# primary_teensy.net
KiCad netlist of a schematic drawn in EAGLE
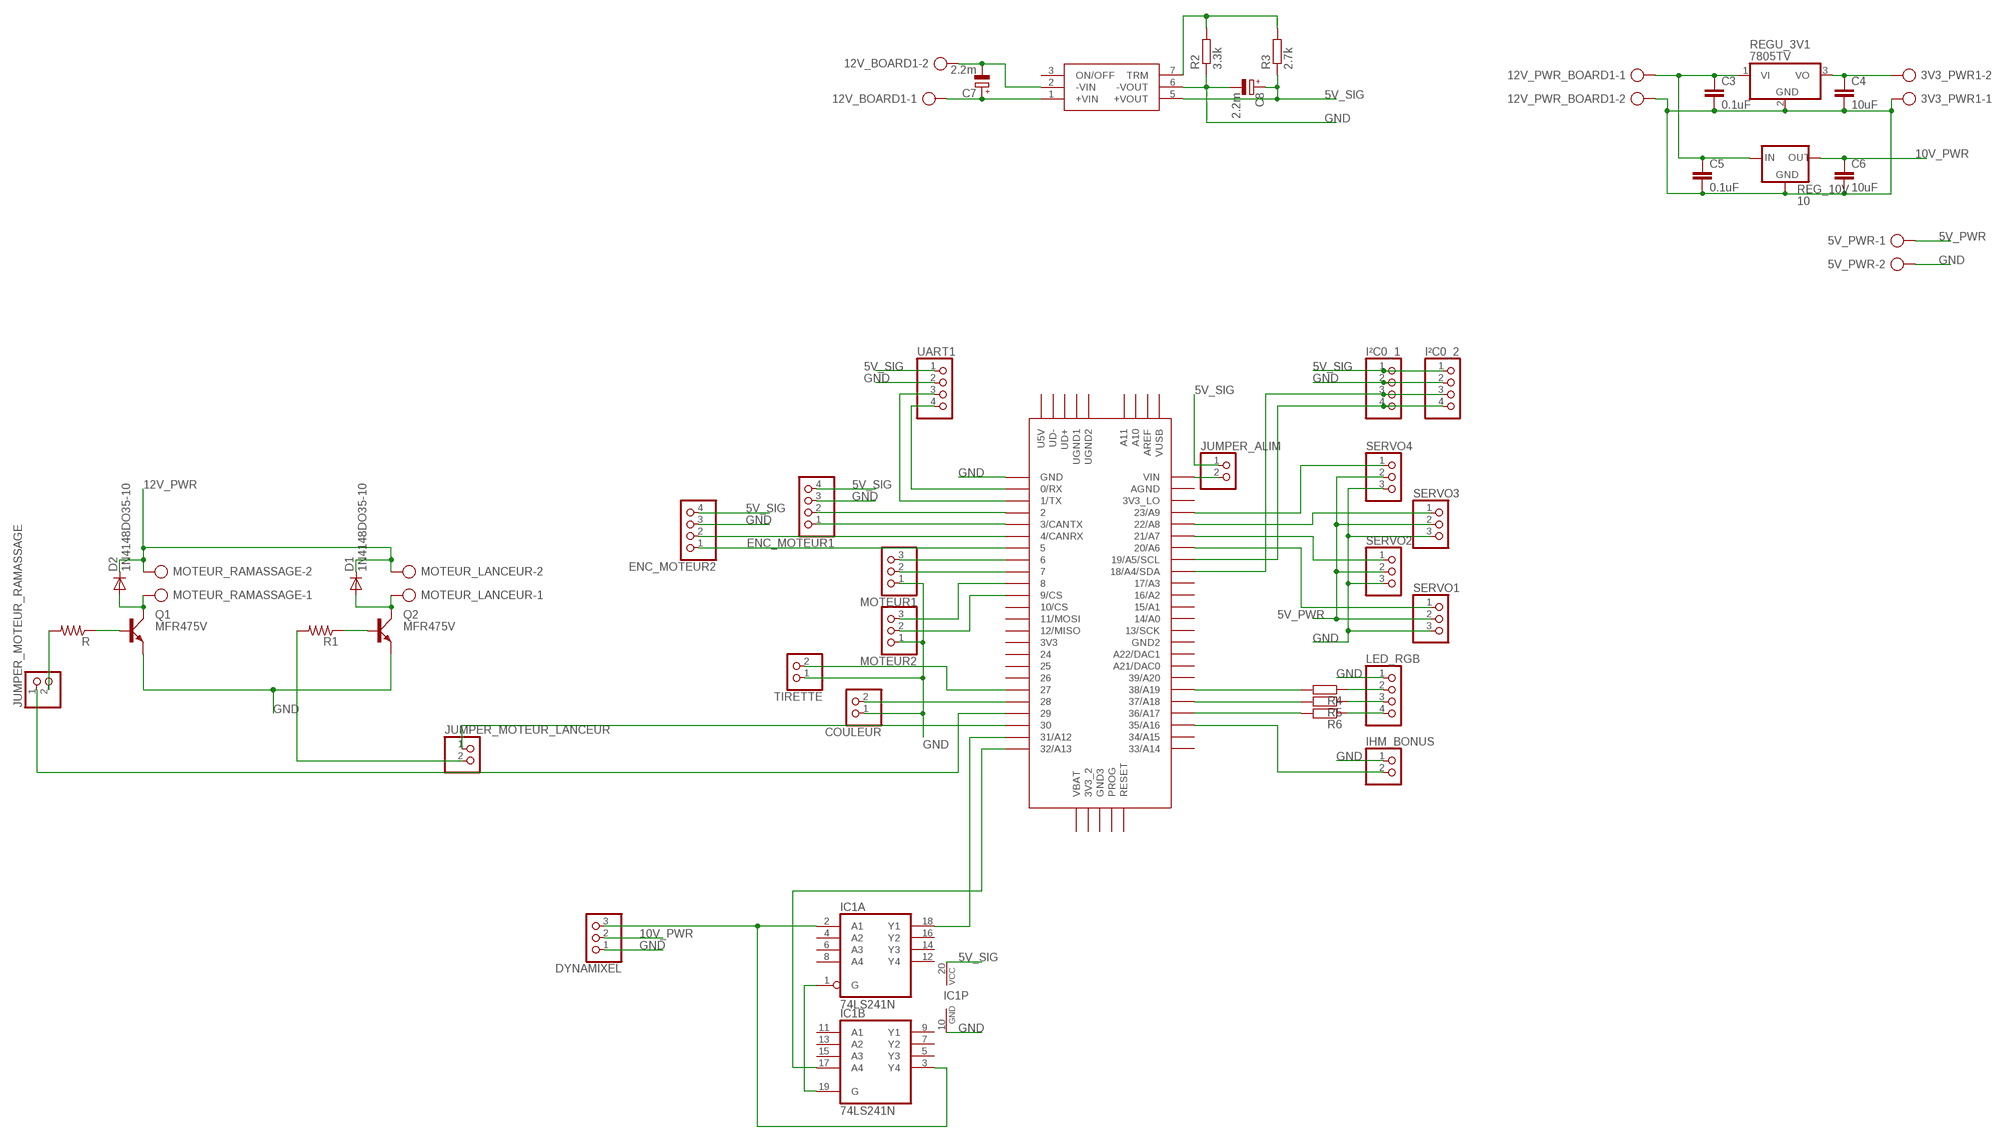
[diagram p0: schematic, sheet 1]

(export (version "E")
  (design (tool "Eeschema 10.0.6"))
  (components
    (comp (ref "3V3_PWR1")
      (value "AK300/2")
      (footprint "eagle-import:AK300_2")
      (fields (field (name "OC_FARNELL") "unknown") (field (name "OC_NEWARK") "unknown"))
      (libsource (lib "eagle-import") (part "AK300/2"))
    )
    (comp (ref "5V_PWR")
      (value "AK300/2")
      (footprint "eagle-import:AK300_2")
      (fields (field (name "OC_FARNELL") "unknown") (field (name "OC_NEWARK") "unknown"))
      (libsource (lib "eagle-import") (part "AK300/2"))
    )
    (comp (ref "12V_BOARD1")
      (value "AK300/2")
      (footprint "eagle-import:AK300_2")
      (fields (field (name "OC_FARNELL") "unknown") (field (name "OC_NEWARK") "unknown"))
      (libsource (lib "eagle-import") (part "AK300/2"))
    )
    (comp (ref "12V_PWR_BOARD1")
      (value "AK300/2")
      (footprint "eagle-import:AK300_2")
      (fields (field (name "OC_FARNELL") "unknown") (field (name "OC_NEWARK") "unknown"))
      (libsource (lib "eagle-import") (part "AK300/2"))
    )
    (comp (ref "C3")
      (value "0.1uF")
      (footprint "eagle-import:C050-025X075")
      (libsource (lib "eagle-import") (part "C-EU050-025X075"))
    )
    (comp (ref "C4")
      (value "10uF")
      (footprint "eagle-import:C050-025X075")
      (libsource (lib "eagle-import") (part "C-EU050-025X075"))
    )
    (comp (ref "C5")
      (value "0.1uF")
      (footprint "eagle-import:C050-025X075")
      (libsource (lib "eagle-import") (part "C-EU050-025X075"))
    )
    (comp (ref "C6")
      (value "10uF")
      (footprint "eagle-import:C050-025X075")
      (libsource (lib "eagle-import") (part "C-EU050-025X075"))
    )
    (comp (ref "C7")
      (value "2.2m")
      (footprint "eagle-import:E5-13")
      (libsource (lib "eagle-import") (part "CPOL-EUE5-13"))
    )
    (comp (ref "C8")
      (value "2.2m")
      (footprint "eagle-import:E5-13")
      (libsource (lib "eagle-import") (part "CPOL-EUE5-13"))
    )
    (comp (ref "COULEUR")
      (value "PINHD-1X2")
      (footprint "eagle-import:1X02")
      (libsource (lib "eagle-import") (part "PINHD-1X2"))
    )
    (comp (ref "D1")
      (value "1N4148DO35-10")
      (footprint "eagle-import:DO35-10")
      (libsource (lib "eagle-import") (part "1N4148DO35-10"))
    )
    (comp (ref "D2")
      (value "1N4148DO35-10")
      (footprint "eagle-import:DO35-10")
      (libsource (lib "eagle-import") (part "1N4148DO35-10"))
    )
    (comp (ref "DYNAMIXEL")
      (value "PINHD-1X3")
      (footprint "eagle-import:1X03")
      (libsource (lib "eagle-import") (part "PINHD-1X3"))
    )
    (comp (ref "ENC_MOTEUR1")
      (value "PINHD-1X4")
      (footprint "eagle-import:1X04")
      (libsource (lib "eagle-import") (part "PINHD-1X4"))
    )
    (comp (ref "ENC_MOTEUR2")
      (value "PINHD-1X4")
      (footprint "eagle-import:1X04")
      (libsource (lib "eagle-import") (part "PINHD-1X4"))
    )
    (comp (ref "IC1")
      (value "74LS241N")
      (footprint "eagle-import:DIL20")
      (libsource (lib "eagle-import") (part "74241NLS"))
    )
    (comp (ref "IHM_BONUS")
      (value "PINHD-1X2")
      (footprint "eagle-import:1X02")
      (libsource (lib "eagle-import") (part "PINHD-1X2"))
    )
    (comp (ref "I²C0_1")
      (value "PINHD-1X4")
      (footprint "eagle-import:1X04")
      (libsource (lib "eagle-import") (part "PINHD-1X4"))
    )
    (comp (ref "I²C0_2")
      (value "PINHD-1X4")
      (footprint "eagle-import:1X04")
      (libsource (lib "eagle-import") (part "PINHD-1X4"))
    )
    (comp (ref "JUMPER_ALIM")
      (value "PINHD-1X2")
      (footprint "eagle-import:1X02")
      (libsource (lib "eagle-import") (part "PINHD-1X2"))
    )
    (comp (ref "JUMPER_MOTEUR_LANCEUR")
      (value "PINHD-1X2")
      (footprint "eagle-import:1X02")
      (libsource (lib "eagle-import") (part "PINHD-1X2"))
    )
    (comp (ref "JUMPER_MOTEUR_RAMASSAGE")
      (value "PINHD-1X2")
      (footprint "eagle-import:1X02")
      (libsource (lib "eagle-import") (part "PINHD-1X2"))
    )
    (comp (ref "LED_RGB")
      (value "PINHD-1X4")
      (footprint "eagle-import:1X04")
      (libsource (lib "eagle-import") (part "PINHD-1X4"))
    )
    (comp (ref "MOTEUR1")
      (value "PINHD-1X3")
      (footprint "eagle-import:1X03")
      (libsource (lib "eagle-import") (part "PINHD-1X3"))
    )
    (comp (ref "MOTEUR2")
      (value "PINHD-1X3")
      (footprint "eagle-import:1X03")
      (libsource (lib "eagle-import") (part "PINHD-1X3"))
    )
    (comp (ref "MOTEUR_LANCEUR")
      (value "AK300/2")
      (footprint "eagle-import:AK300_2")
      (fields (field (name "OC_FARNELL") "unknown") (field (name "OC_NEWARK") "unknown"))
      (libsource (lib "eagle-import") (part "AK300/2"))
    )
    (comp (ref "MOTEUR_RAMASSAGE")
      (value "AK300/2")
      (footprint "eagle-import:AK300_2")
      (fields (field (name "OC_FARNELL") "unknown") (field (name "OC_NEWARK") "unknown"))
      (libsource (lib "eagle-import") (part "AK300/2"))
    )
    (comp (ref "Q1")
      (value "MFR475V")
      (footprint "eagle-import:TO220AV")
      (libsource (lib "eagle-import") (part "MFR4V75"))
    )
    (comp (ref "Q2")
      (value "MFR475V")
      (footprint "eagle-import:TO220AV")
      (libsource (lib "eagle-import") (part "MFR4V75"))
    )
    (comp (ref "R")
      (value "RESISTORAXIAL-0.3")
      (footprint "eagle-import:AXIAL-0.3")
      (libsource (lib "eagle-import") (part "RESISTORAXIAL-0.3"))
    )
    (comp (ref "R1")
      (value "RESISTORAXIAL-0.3")
      (footprint "eagle-import:AXIAL-0.3")
      (libsource (lib "eagle-import") (part "RESISTORAXIAL-0.3"))
    )
    (comp (ref "R2")
      (value "3.3k")
      (footprint "eagle-import:0207_7")
      (libsource (lib "eagle-import") (part "R-EU_0207/7"))
    )
    (comp (ref "R3")
      (value "2.7k")
      (footprint "eagle-import:0207_7")
      (libsource (lib "eagle-import") (part "R-EU_0207/7"))
    )
    (comp (ref "R4")
      (value "R-EU_0207/7")
      (footprint "eagle-import:0207_7")
      (libsource (lib "eagle-import") (part "R-EU_0207/7"))
    )
    (comp (ref "R5")
      (value "R-EU_0207/7")
      (footprint "eagle-import:0207_7")
      (libsource (lib "eagle-import") (part "R-EU_0207/7"))
    )
    (comp (ref "R6")
      (value "R-EU_0207/7")
      (footprint "eagle-import:0207_7")
      (libsource (lib "eagle-import") (part "R-EU_0207/7"))
    )
    (comp (ref "REGU_3V1")
      (value "7805TV")
      (footprint "eagle-import:TO220V")
      (libsource (lib "eagle-import") (part "78TV05"))
    )
    (comp (ref "REG_10V")
      (value "10")
      (footprint "eagle-import:78XXS")
      (libsource (lib "eagle-import") (part "78XXS"))
    )
    (comp (ref "SERVO1")
      (value "PINHD-1X3")
      (footprint "eagle-import:1X03")
      (libsource (lib "eagle-import") (part "PINHD-1X3"))
    )
    (comp (ref "SERVO2")
      (value "PINHD-1X3")
      (footprint "eagle-import:1X03")
      (libsource (lib "eagle-import") (part "PINHD-1X3"))
    )
    (comp (ref "SERVO3")
      (value "PINHD-1X3")
      (footprint "eagle-import:1X03")
      (libsource (lib "eagle-import") (part "PINHD-1X3"))
    )
    (comp (ref "SERVO4")
      (value "PINHD-1X3")
      (footprint "eagle-import:1X03")
      (libsource (lib "eagle-import") (part "PINHD-1X3"))
    )
    (comp (ref "TIRETTE")
      (value "PINHD-1X2")
      (footprint "eagle-import:1X02")
      (libsource (lib "eagle-import") (part "PINHD-1X2"))
    )
    (comp (ref "U$1")
      (value "TEENSY_3.5/3.6")
      (footprint "eagle-import:TEENSY_3.5_3.6")
      (libsource (lib "eagle-import") (part "TEENSY_3.5/3.6"))
    )
    (comp (ref "U$3")
      (value "TEN25-1211TEN25-1211")
      (footprint "eagle-import:TEN25")
      (libsource (lib "eagle-import") (part "TEN25-1211TEN25-1211"))
    )
    (comp (ref "UART1")
      (value "PINHD-1X4")
      (footprint "eagle-import:1X04")
      (libsource (lib "eagle-import") (part "PINHD-1X4"))
    )
  )
  (nets
    (net (code "1") (name "/5V_PWR") (class "Default")
      (node (ref "5V_PWR") (pin "1") (pinfunction "KL_1") (pintype "passive"))
      (node (ref "SERVO1") (pin "2") (pinfunction "2_2") (pintype "passive"))
      (node (ref "SERVO2") (pin "2") (pinfunction "2_2") (pintype "passive"))
      (node (ref "SERVO3") (pin "2") (pinfunction "2_2") (pintype "passive"))
      (node (ref "SERVO4") (pin "2") (pinfunction "2_2") (pintype "passive"))
    )
    (net (code "2") (name "/5V_SIG") (class "Default")
      (node (ref "C8") (pin "+") (pinfunction "+_+") (pintype "passive"))
      (node (ref "ENC_MOTEUR1") (pin "4") (pinfunction "4_4") (pintype "passive"))
      (node (ref "ENC_MOTEUR2") (pin "4") (pinfunction "4_4") (pintype "passive"))
      (node (ref "IC1") (pin "20") (pinfunction "VCC_20") (pintype "power_in"))
      (node (ref "I²C0_1") (pin "1") (pinfunction "1_1") (pintype "passive"))
      (node (ref "I²C0_2") (pin "1") (pinfunction "1_1") (pintype "passive"))
      (node (ref "JUMPER_ALIM") (pin "1") (pinfunction "1_1") (pintype "passive"))
      (node (ref "R3") (pin "1") (pinfunction "1_1") (pintype "passive"))
      (node (ref "U$3") (pin "5") (pinfunction "+VOUT_5") (pintype "bidirectional"))
      (node (ref "UART1") (pin "1") (pinfunction "1_1") (pintype "passive"))
    )
    (net (code "3") (name "/10V_PWR") (class "Default")
      (node (ref "C6") (pin "1") (pinfunction "1_1") (pintype "passive"))
      (node (ref "DYNAMIXEL") (pin "2") (pinfunction "2_2") (pintype "passive"))
      (node (ref "REG_10V") (pin "OUT") (pinfunction "OUT_OUT") (pintype "passive"))
    )
    (net (code "4") (name "/12V_PWR") (class "Default")
      (node (ref "12V_PWR_BOARD1") (pin "1") (pinfunction "KL_1") (pintype "passive"))
      (node (ref "C3") (pin "1") (pinfunction "1_1") (pintype "passive"))
      (node (ref "C5") (pin "1") (pinfunction "1_1") (pintype "passive"))
      (node (ref "D1") (pin "C") (pinfunction "C_C") (pintype "passive"))
      (node (ref "D2") (pin "C") (pinfunction "C_C") (pintype "passive"))
      (node (ref "MOTEUR_LANCEUR") (pin "2") (pinfunction "KL_2") (pintype "passive"))
      (node (ref "MOTEUR_RAMASSAGE") (pin "2") (pinfunction "KL_2") (pintype "passive"))
      (node (ref "REGU_3V1") (pin "1") (pinfunction "VI_1") (pintype "input"))
      (node (ref "REG_10V") (pin "IN") (pinfunction "IN_IN") (pintype "input"))
    )
    (net (code "5") (name "/GND") (class "Default")
      (node (ref "12V_PWR_BOARD1") (pin "2") (pinfunction "KL_2") (pintype "passive"))
      (node (ref "3V3_PWR1") (pin "1") (pinfunction "KL_1") (pintype "passive"))
      (node (ref "5V_PWR") (pin "2") (pinfunction "KL_2") (pintype "passive"))
      (node (ref "C3") (pin "2") (pinfunction "2_2") (pintype "passive"))
      (node (ref "C4") (pin "2") (pinfunction "2_2") (pintype "passive"))
      (node (ref "C5") (pin "2") (pinfunction "2_2") (pintype "passive"))
      (node (ref "C6") (pin "2") (pinfunction "2_2") (pintype "passive"))
      (node (ref "C8") (pin "-") (pinfunction "-_-") (pintype "passive"))
      (node (ref "COULEUR") (pin "1") (pinfunction "1_1") (pintype "passive"))
      (node (ref "DYNAMIXEL") (pin "1") (pinfunction "1_1") (pintype "passive"))
      (node (ref "ENC_MOTEUR1") (pin "3") (pinfunction "3_3") (pintype "passive"))
      (node (ref "ENC_MOTEUR2") (pin "3") (pinfunction "3_3") (pintype "passive"))
      (node (ref "IC1") (pin "10") (pinfunction "GND_10") (pintype "power_in"))
      (node (ref "IHM_BONUS") (pin "1") (pinfunction "1_1") (pintype "passive"))
      (node (ref "I²C0_1") (pin "2") (pinfunction "2_2") (pintype "passive"))
      (node (ref "I²C0_2") (pin "2") (pinfunction "2_2") (pintype "passive"))
      (node (ref "LED_RGB") (pin "1") (pinfunction "1_1") (pintype "passive"))
      (node (ref "MOTEUR1") (pin "1") (pinfunction "1_1") (pintype "passive"))
      (node (ref "MOTEUR2") (pin "1") (pinfunction "1_1") (pintype "passive"))
      (node (ref "Q1") (pin "E") (pinfunction "E_E") (pintype "passive"))
      (node (ref "Q2") (pin "E") (pinfunction "E_E") (pintype "passive"))
      (node (ref "R2") (pin "1") (pinfunction "1_1") (pintype "passive"))
      (node (ref "REGU_3V1") (pin "2") (pinfunction "GND_2") (pintype "passive"))
      (node (ref "REG_10V") (pin "GND") (pinfunction "GND_GND") (pintype "input"))
      (node (ref "SERVO1") (pin "3") (pinfunction "3_3") (pintype "passive"))
      (node (ref "SERVO2") (pin "3") (pinfunction "3_3") (pintype "passive"))
      (node (ref "SERVO3") (pin "3") (pinfunction "3_3") (pintype "passive"))
      (node (ref "SERVO4") (pin "3") (pinfunction "3_3") (pintype "passive"))
      (node (ref "TIRETTE") (pin "1") (pinfunction "1_1") (pintype "passive"))
      (node (ref "U$1") (pin "GND") (pinfunction "GND_GND") (pintype "bidirectional"))
      (node (ref "U$3") (pin "6") (pinfunction "-VOUT_6") (pintype "bidirectional"))
      (node (ref "UART1") (pin "2") (pinfunction "2_2") (pintype "passive"))
    )
    (net (code "6") (name "Net-(3V3_PWR1B-KL)") (class "Default")
      (node (ref "3V3_PWR1") (pin "2") (pinfunction "KL_2") (pintype "passive"))
      (node (ref "C4") (pin "1") (pinfunction "1_1") (pintype "passive"))
      (node (ref "REGU_3V1") (pin "3") (pinfunction "VO_3") (pintype "passive"))
    )
    (net (code "7") (name "Net-(12V_BOARD1A-KL)") (class "Default")
      (node (ref "12V_BOARD1") (pin "1") (pinfunction "KL_1") (pintype "passive"))
      (node (ref "C7") (pin "+") (pinfunction "+_+") (pintype "passive"))
      (node (ref "U$3") (pin "1") (pinfunction "+VIN_1") (pintype "bidirectional"))
    )
    (net (code "8") (name "Net-(12V_BOARD1B-KL)") (class "Default")
      (node (ref "12V_BOARD1") (pin "2") (pinfunction "KL_2") (pintype "passive"))
      (node (ref "C7") (pin "-") (pinfunction "-_-") (pintype "passive"))
      (node (ref "U$3") (pin "2") (pinfunction "-VIN_2") (pintype "bidirectional"))
    )
    (net (code "9") (name "Net-(COULEUR-Pad2)") (class "Default")
      (node (ref "COULEUR") (pin "2") (pinfunction "2_2") (pintype "passive"))
      (node (ref "U$1") (pin "28") (pinfunction "28_28") (pintype "bidirectional"))
    )
    (net (code "10") (name "Net-(ENC_MOTEUR1-Pad1)") (class "Default")
      (node (ref "ENC_MOTEUR1") (pin "1") (pinfunction "1_1") (pintype "passive"))
      (node (ref "U$1") (pin "3/CANTX") (pinfunction "3/CANTX_3/CANTX") (pintype "bidirectional"))
    )
    (net (code "11") (name "Net-(ENC_MOTEUR1-Pad2)") (class "Default")
      (node (ref "ENC_MOTEUR1") (pin "2") (pinfunction "2_2") (pintype "passive"))
      (node (ref "U$1") (pin "2") (pinfunction "2_2") (pintype "bidirectional"))
    )
    (net (code "12") (name "Net-(ENC_MOTEUR2-Pad1)") (class "Default")
      (node (ref "ENC_MOTEUR2") (pin "1") (pinfunction "1_1") (pintype "passive"))
      (node (ref "U$1") (pin "5") (pinfunction "5_5") (pintype "bidirectional"))
    )
    (net (code "13") (name "Net-(ENC_MOTEUR2-Pad2)") (class "Default")
      (node (ref "ENC_MOTEUR2") (pin "2") (pinfunction "2_2") (pintype "passive"))
      (node (ref "U$1") (pin "4/CANRX") (pinfunction "4/CANRX_4/CANRX") (pintype "bidirectional"))
    )
    (net (code "14") (name "Net-(IC1A-A1)") (class "Default")
      (node (ref "DYNAMIXEL") (pin "3") (pinfunction "3_3") (pintype "passive"))
      (node (ref "IC1") (pin "2") (pinfunction "A1_2") (pintype "input"))
      (node (ref "IC1") (pin "3") (pinfunction "Y4_3") (pintype "tri_state"))
    )
    (net (code "15") (name "Net-(IC1A-G)") (class "Default")
      (node (ref "IC1") (pin "1") (pinfunction "G_1") (pintype "input"))
      (node (ref "IC1") (pin "19") (pinfunction "G_19") (pintype "input"))
    )
    (net (code "16") (name "Net-(IC1A-Y1)") (class "Default")
      (node (ref "IC1") (pin "18") (pinfunction "Y1_18") (pintype "tri_state"))
      (node (ref "U$1") (pin "31/A12") (pinfunction "31/A12_31/A12") (pintype "bidirectional"))
    )
    (net (code "17") (name "Net-(IC1B-A4)") (class "Default")
      (node (ref "IC1") (pin "17") (pinfunction "A4_17") (pintype "input"))
      (node (ref "U$1") (pin "32/A13") (pinfunction "32/A13_32/A13") (pintype "bidirectional"))
    )
    (net (code "18") (name "Net-(IHM_BONUS-Pad2)") (class "Default")
      (node (ref "IHM_BONUS") (pin "2") (pinfunction "2_2") (pintype "passive"))
      (node (ref "U$1") (pin "35/A16") (pinfunction "35/A16_35/A16") (pintype "bidirectional"))
    )
    (net (code "19") (name "Net-(I²C0_1-Pad3)") (class "Default")
      (node (ref "I²C0_1") (pin "3") (pinfunction "3_3") (pintype "passive"))
      (node (ref "I²C0_2") (pin "3") (pinfunction "3_3") (pintype "passive"))
      (node (ref "U$1") (pin "18/A4/SDA") (pinfunction "18/A4/SDA_18/A4/SDA") (pintype "bidirectional"))
    )
    (net (code "20") (name "Net-(I²C0_1-Pad4)") (class "Default")
      (node (ref "I²C0_1") (pin "4") (pinfunction "4_4") (pintype "passive"))
      (node (ref "I²C0_2") (pin "4") (pinfunction "4_4") (pintype "passive"))
      (node (ref "U$1") (pin "19/A5/SCL") (pinfunction "19/A5/SCL_19/A5/SCL") (pintype "bidirectional"))
    )
    (net (code "21") (name "Net-(JUMPER_ALIM-Pad2)") (class "Default")
      (node (ref "JUMPER_ALIM") (pin "2") (pinfunction "2_2") (pintype "passive"))
      (node (ref "U$1") (pin "VIN") (pinfunction "VIN_VIN") (pintype "bidirectional"))
    )
    (net (code "22") (name "Net-(JUMPER_MOTEUR_LANCEUR-Pad1)") (class "Default")
      (node (ref "JUMPER_MOTEUR_LANCEUR") (pin "1") (pinfunction "1_1") (pintype "passive"))
      (node (ref "U$1") (pin "30") (pinfunction "30_30") (pintype "bidirectional"))
    )
    (net (code "23") (name "Net-(JUMPER_MOTEUR_RAMASSAGE-Pad1)") (class "Default")
      (node (ref "JUMPER_MOTEUR_RAMASSAGE") (pin "1") (pinfunction "1_1") (pintype "passive"))
      (node (ref "U$1") (pin "29") (pinfunction "29_29") (pintype "bidirectional"))
    )
    (net (code "24") (name "Net-(LED_RGB-Pad2)") (class "Default")
      (node (ref "LED_RGB") (pin "2") (pinfunction "2_2") (pintype "passive"))
      (node (ref "R4") (pin "1") (pinfunction "1_1") (pintype "passive"))
    )
    (net (code "25") (name "Net-(LED_RGB-Pad3)") (class "Default")
      (node (ref "LED_RGB") (pin "3") (pinfunction "3_3") (pintype "passive"))
      (node (ref "R5") (pin "1") (pinfunction "1_1") (pintype "passive"))
    )
    (net (code "26") (name "Net-(LED_RGB-Pad4)") (class "Default")
      (node (ref "LED_RGB") (pin "4") (pinfunction "4_4") (pintype "passive"))
      (node (ref "R6") (pin "1") (pinfunction "1_1") (pintype "passive"))
    )
    (net (code "27") (name "Net-(MOTEUR1-Pad2)") (class "Default")
      (node (ref "MOTEUR1") (pin "2") (pinfunction "2_2") (pintype "passive"))
      (node (ref "U$1") (pin "7") (pinfunction "7_7") (pintype "bidirectional"))
    )
    (net (code "28") (name "Net-(MOTEUR1-Pad3)") (class "Default")
      (node (ref "MOTEUR1") (pin "3") (pinfunction "3_3") (pintype "passive"))
      (node (ref "U$1") (pin "6") (pinfunction "6_6") (pintype "bidirectional"))
    )
    (net (code "29") (name "Net-(MOTEUR2-Pad2)") (class "Default")
      (node (ref "MOTEUR2") (pin "2") (pinfunction "2_2") (pintype "passive"))
      (node (ref "U$1") (pin "9/CS") (pinfunction "9/CS_9/CS") (pintype "bidirectional"))
    )
    (net (code "30") (name "Net-(MOTEUR2-Pad3)") (class "Default")
      (node (ref "MOTEUR2") (pin "3") (pinfunction "3_3") (pintype "passive"))
      (node (ref "U$1") (pin "8") (pinfunction "8_8") (pintype "bidirectional"))
    )
    (net (code "31") (name "Net-(MOTEUR_LANCEURA-KL)") (class "Default")
      (node (ref "D1") (pin "A") (pinfunction "A_A") (pintype "passive"))
      (node (ref "MOTEUR_LANCEUR") (pin "1") (pinfunction "KL_1") (pintype "passive"))
      (node (ref "Q2") (pin "C") (pinfunction "C_C") (pintype "passive"))
    )
    (net (code "32") (name "Net-(MOTEUR_RAMASSAGEA-KL)") (class "Default")
      (node (ref "D2") (pin "A") (pinfunction "A_A") (pintype "passive"))
      (node (ref "MOTEUR_RAMASSAGE") (pin "1") (pinfunction "KL_1") (pintype "passive"))
      (node (ref "Q1") (pin "C") (pinfunction "C_C") (pintype "passive"))
    )
    (net (code "33") (name "Net-(R-1)") (class "Default")
      (node (ref "Q1") (pin "B") (pinfunction "B_B") (pintype "passive"))
      (node (ref "R") (pin "P$1") (pinfunction "1_P$1") (pintype "passive"))
    )
    (net (code "34") (name "Net-(R-2)") (class "Default")
      (node (ref "JUMPER_MOTEUR_RAMASSAGE") (pin "2") (pinfunction "2_2") (pintype "passive"))
      (node (ref "R") (pin "P$2") (pinfunction "2_P$2") (pintype "passive"))
    )
    (net (code "35") (name "Net-(R1-1)") (class "Default")
      (node (ref "Q2") (pin "B") (pinfunction "B_B") (pintype "passive"))
      (node (ref "R1") (pin "P$1") (pinfunction "1_P$1") (pintype "passive"))
    )
    (net (code "36") (name "Net-(R1-2)") (class "Default")
      (node (ref "JUMPER_MOTEUR_LANCEUR") (pin "2") (pinfunction "2_2") (pintype "passive"))
      (node (ref "R1") (pin "P$2") (pinfunction "2_P$2") (pintype "passive"))
    )
    (net (code "37") (name "Net-(R4-Pad2)") (class "Default")
      (node (ref "R4") (pin "2") (pinfunction "2_2") (pintype "passive"))
      (node (ref "U$1") (pin "38/A19") (pinfunction "38/A19_38/A19") (pintype "bidirectional"))
    )
    (net (code "38") (name "Net-(R5-Pad2)") (class "Default")
      (node (ref "R5") (pin "2") (pinfunction "2_2") (pintype "passive"))
      (node (ref "U$1") (pin "37/A18") (pinfunction "37/A18_37/A18") (pintype "bidirectional"))
    )
    (net (code "39") (name "Net-(R6-Pad2)") (class "Default")
      (node (ref "R6") (pin "2") (pinfunction "2_2") (pintype "passive"))
      (node (ref "U$1") (pin "36/A17") (pinfunction "36/A17_36/A17") (pintype "bidirectional"))
    )
    (net (code "40") (name "Net-(SERVO1-Pad1)") (class "Default")
      (node (ref "SERVO1") (pin "1") (pinfunction "1_1") (pintype "passive"))
      (node (ref "U$1") (pin "20/A6") (pinfunction "20/A6_20/A6") (pintype "bidirectional"))
    )
    (net (code "41") (name "Net-(SERVO2-Pad1)") (class "Default")
      (node (ref "SERVO2") (pin "1") (pinfunction "1_1") (pintype "passive"))
      (node (ref "U$1") (pin "21/A7") (pinfunction "21/A7_21/A7") (pintype "bidirectional"))
    )
    (net (code "42") (name "Net-(SERVO3-Pad1)") (class "Default")
      (node (ref "SERVO3") (pin "1") (pinfunction "1_1") (pintype "passive"))
      (node (ref "U$1") (pin "22/A8") (pinfunction "22/A8_22/A8") (pintype "bidirectional"))
    )
    (net (code "43") (name "Net-(SERVO4-Pad1)") (class "Default")
      (node (ref "SERVO4") (pin "1") (pinfunction "1_1") (pintype "passive"))
      (node (ref "U$1") (pin "23/A9") (pinfunction "23/A9_23/A9") (pintype "bidirectional"))
    )
    (net (code "44") (name "Net-(TIRETTE-Pad2)") (class "Default")
      (node (ref "TIRETTE") (pin "2") (pinfunction "2_2") (pintype "passive"))
      (node (ref "U$1") (pin "27") (pinfunction "27_27") (pintype "bidirectional"))
    )
    (net (code "45") (name "Net-(U$1-Pad0{slash}RX)") (class "Default")
      (node (ref "U$1") (pin "0/RX") (pinfunction "0/RX_0/RX") (pintype "bidirectional"))
      (node (ref "UART1") (pin "4") (pinfunction "4_4") (pintype "passive"))
    )
    (net (code "46") (name "Net-(U$1-Pad1{slash}TX)") (class "Default")
      (node (ref "U$1") (pin "1/TX") (pinfunction "1/TX_1/TX") (pintype "bidirectional"))
      (node (ref "UART1") (pin "3") (pinfunction "3_3") (pintype "passive"))
    )
    (net (code "47") (name "Net-(U$3-TRM)") (class "Default")
      (node (ref "R2") (pin "2") (pinfunction "2_2") (pintype "passive"))
      (node (ref "R3") (pin "2") (pinfunction "2_2") (pintype "passive"))
      (node (ref "U$3") (pin "7") (pinfunction "TRM_7") (pintype "bidirectional"))
    )
    (net (code "48") (name "unconnected-(IC1A-A2-Pad4)") (class "Default")
      (node (ref "IC1") (pin "4") (pinfunction "A2_4") (pintype "input"))
    )
    (net (code "49") (name "unconnected-(IC1A-A3-Pad6)") (class "Default")
      (node (ref "IC1") (pin "6") (pinfunction "A3_6") (pintype "input"))
    )
    (net (code "50") (name "unconnected-(IC1A-A4-Pad8)") (class "Default")
      (node (ref "IC1") (pin "8") (pinfunction "A4_8") (pintype "input"))
    )
    (net (code "51") (name "unconnected-(IC1A-Y2-Pad16)") (class "Default")
      (node (ref "IC1") (pin "16") (pinfunction "Y2_16") (pintype "tri_state"))
    )
    (net (code "52") (name "unconnected-(IC1A-Y3-Pad14)") (class "Default")
      (node (ref "IC1") (pin "14") (pinfunction "Y3_14") (pintype "tri_state"))
    )
    (net (code "53") (name "unconnected-(IC1A-Y4-Pad12)") (class "Default")
      (node (ref "IC1") (pin "12") (pinfunction "Y4_12") (pintype "tri_state"))
    )
    (net (code "54") (name "unconnected-(IC1B-A1-Pad11)") (class "Default")
      (node (ref "IC1") (pin "11") (pinfunction "A1_11") (pintype "input"))
    )
    (net (code "55") (name "unconnected-(IC1B-A2-Pad13)") (class "Default")
      (node (ref "IC1") (pin "13") (pinfunction "A2_13") (pintype "input"))
    )
    (net (code "56") (name "unconnected-(IC1B-A3-Pad15)") (class "Default")
      (node (ref "IC1") (pin "15") (pinfunction "A3_15") (pintype "input"))
    )
    (net (code "57") (name "unconnected-(IC1B-Y1-Pad9)") (class "Default")
      (node (ref "IC1") (pin "9") (pinfunction "Y1_9") (pintype "tri_state"))
    )
    (net (code "58") (name "unconnected-(IC1B-Y2-Pad7)") (class "Default")
      (node (ref "IC1") (pin "7") (pinfunction "Y2_7") (pintype "tri_state"))
    )
    (net (code "59") (name "unconnected-(IC1B-Y3-Pad5)") (class "Default")
      (node (ref "IC1") (pin "5") (pinfunction "Y3_5") (pintype "tri_state"))
    )
    (net (code "60") (name "unconnected-(U$1-A21{slash}DAC0-Pad21{slash}DAC0)") (class "Default")
      (node (ref "U$1") (pin "21/DAC0") (pinfunction "A21/DAC0_21/DAC0") (pintype "bidirectional"))
    )
    (net (code "61") (name "unconnected-(U$1-Pad3V3)") (class "Default")
      (node (ref "U$1") (pin "3V3") (pinfunction "3V3_3V3") (pintype "bidirectional"))
    )
    (net (code "62") (name "unconnected-(U$1-Pad3V3_2)") (class "Default")
      (node (ref "U$1") (pin "3V3_2") (pinfunction "3V3_2_3V3_2") (pintype "bidirectional"))
    )
    (net (code "63") (name "unconnected-(U$1-Pad3V3_LO)") (class "Default")
      (node (ref "U$1") (pin "3V3_LO") (pinfunction "3V3_LO_3V3_LO") (pintype "bidirectional"))
    )
    (net (code "64") (name "unconnected-(U$1-Pad10{slash}CS)") (class "Default")
      (node (ref "U$1") (pin "10/CS") (pinfunction "10/CS_10/CS") (pintype "bidirectional"))
    )
    (net (code "65") (name "unconnected-(U$1-Pad11{slash}MOSI)") (class "Default")
      (node (ref "U$1") (pin "11/MOSI") (pinfunction "11/MOSI_11/MOSI") (pintype "bidirectional"))
    )
    (net (code "66") (name "unconnected-(U$1-Pad12{slash}MISO)") (class "Default")
      (node (ref "U$1") (pin "12/MISO") (pinfunction "12/MISO_12/MISO") (pintype "bidirectional"))
    )
    (net (code "67") (name "unconnected-(U$1-Pad13{slash}SCK)") (class "Default")
      (node (ref "U$1") (pin "13/SCK") (pinfunction "13/SCK_13/SCK") (pintype "bidirectional"))
    )
    (net (code "68") (name "unconnected-(U$1-Pad14{slash}A0)") (class "Default")
      (node (ref "U$1") (pin "14/A0") (pinfunction "14/A0_14/A0") (pintype "bidirectional"))
    )
    (net (code "69") (name "unconnected-(U$1-Pad15{slash}A1)") (class "Default")
      (node (ref "U$1") (pin "15/A1") (pinfunction "15/A1_15/A1") (pintype "bidirectional"))
    )
    (net (code "70") (name "unconnected-(U$1-Pad16{slash}A2)") (class "Default")
      (node (ref "U$1") (pin "16/A2") (pinfunction "16/A2_16/A2") (pintype "bidirectional"))
    )
    (net (code "71") (name "unconnected-(U$1-Pad17{slash}A3)") (class "Default")
      (node (ref "U$1") (pin "17/A3") (pinfunction "17/A3_17/A3") (pintype "bidirectional"))
    )
    (net (code "72") (name "unconnected-(U$1-Pad24)") (class "Default")
      (node (ref "U$1") (pin "24") (pinfunction "24_24") (pintype "bidirectional"))
    )
    (net (code "73") (name "unconnected-(U$1-Pad25)") (class "Default")
      (node (ref "U$1") (pin "25") (pinfunction "25_25") (pintype "bidirectional"))
    )
    (net (code "74") (name "unconnected-(U$1-Pad26)") (class "Default")
      (node (ref "U$1") (pin "26") (pinfunction "26_26") (pintype "bidirectional"))
    )
    (net (code "75") (name "unconnected-(U$1-Pad33{slash}A14)") (class "Default")
      (node (ref "U$1") (pin "33/A14") (pinfunction "33/A14_33/A14") (pintype "bidirectional"))
    )
    (net (code "76") (name "unconnected-(U$1-Pad34{slash}A15)") (class "Default")
      (node (ref "U$1") (pin "34/A15") (pinfunction "34/A15_34/A15") (pintype "bidirectional"))
    )
    (net (code "77") (name "unconnected-(U$1-Pad39{slash}A20)") (class "Default")
      (node (ref "U$1") (pin "39/A20") (pinfunction "39/A20_39/A20") (pintype "bidirectional"))
    )
    (net (code "78") (name "unconnected-(U$1-PadA10)") (class "Default")
      (node (ref "U$1") (pin "A10") (pinfunction "A10_A10") (pintype "bidirectional"))
    )
    (net (code "79") (name "unconnected-(U$1-PadA11)") (class "Default")
      (node (ref "U$1") (pin "A11") (pinfunction "A11_A11") (pintype "bidirectional"))
    )
    (net (code "80") (name "unconnected-(U$1-PadA22{slash}DAC1)") (class "Default")
      (node (ref "U$1") (pin "A22/DAC1") (pinfunction "A22/DAC1_A22/DAC1") (pintype "bidirectional"))
    )
    (net (code "81") (name "unconnected-(U$1-PadAGND)") (class "Default")
      (node (ref "U$1") (pin "AGND") (pinfunction "AGND_AGND") (pintype "bidirectional"))
    )
    (net (code "82") (name "unconnected-(U$1-PadAREF)") (class "Default")
      (node (ref "U$1") (pin "AREF") (pinfunction "AREF_AREF") (pintype "bidirectional"))
    )
    (net (code "83") (name "unconnected-(U$1-PadGND2)") (class "Default")
      (node (ref "U$1") (pin "GND2") (pinfunction "GND2_GND2") (pintype "bidirectional"))
    )
    (net (code "84") (name "unconnected-(U$1-PadGND3)") (class "Default")
      (node (ref "U$1") (pin "GND3") (pinfunction "GND3_GND3") (pintype "bidirectional"))
    )
    (net (code "85") (name "unconnected-(U$1-PadPROG)") (class "Default")
      (node (ref "U$1") (pin "PROG") (pinfunction "PROG_PROG") (pintype "bidirectional"))
    )
    (net (code "86") (name "unconnected-(U$1-PadRESET)") (class "Default")
      (node (ref "U$1") (pin "RESET") (pinfunction "RESET_RESET") (pintype "bidirectional"))
    )
    (net (code "87") (name "unconnected-(U$1-PadU5V)") (class "Default")
      (node (ref "U$1") (pin "U5V") (pinfunction "U5V_U5V") (pintype "bidirectional"))
    )
    (net (code "88") (name "unconnected-(U$1-PadUD+)") (class "Default")
      (node (ref "U$1") (pin "UD+") (pinfunction "UD+_UD+") (pintype "bidirectional"))
    )
    (net (code "89") (name "unconnected-(U$1-PadUD-)") (class "Default")
      (node (ref "U$1") (pin "UD-") (pinfunction "UD-_UD-") (pintype "bidirectional"))
    )
    (net (code "90") (name "unconnected-(U$1-PadUGND1)") (class "Default")
      (node (ref "U$1") (pin "UGND1") (pinfunction "UGND1_UGND1") (pintype "bidirectional"))
    )
    (net (code "91") (name "unconnected-(U$1-PadUGND2)") (class "Default")
      (node (ref "U$1") (pin "UGND2") (pinfunction "UGND2_UGND2") (pintype "bidirectional"))
    )
    (net (code "92") (name "unconnected-(U$1-PadVBAT)") (class "Default")
      (node (ref "U$1") (pin "VBAT") (pinfunction "VBAT_VBAT") (pintype "bidirectional"))
    )
    (net (code "93") (name "unconnected-(U$1-PadVUSB)") (class "Default")
      (node (ref "U$1") (pin "VUSB") (pinfunction "VUSB_VUSB") (pintype "bidirectional"))
    )
    (net (code "94") (name "unconnected-(U$3-ON{slash}OFF-Pad3)") (class "Default")
      (node (ref "U$3") (pin "3") (pinfunction "ON/OFF_3") (pintype "bidirectional"))
    )
  )
)
